# PainRegister_PWM.net
KiCad netlist of a schematic drawn in Altium Designer
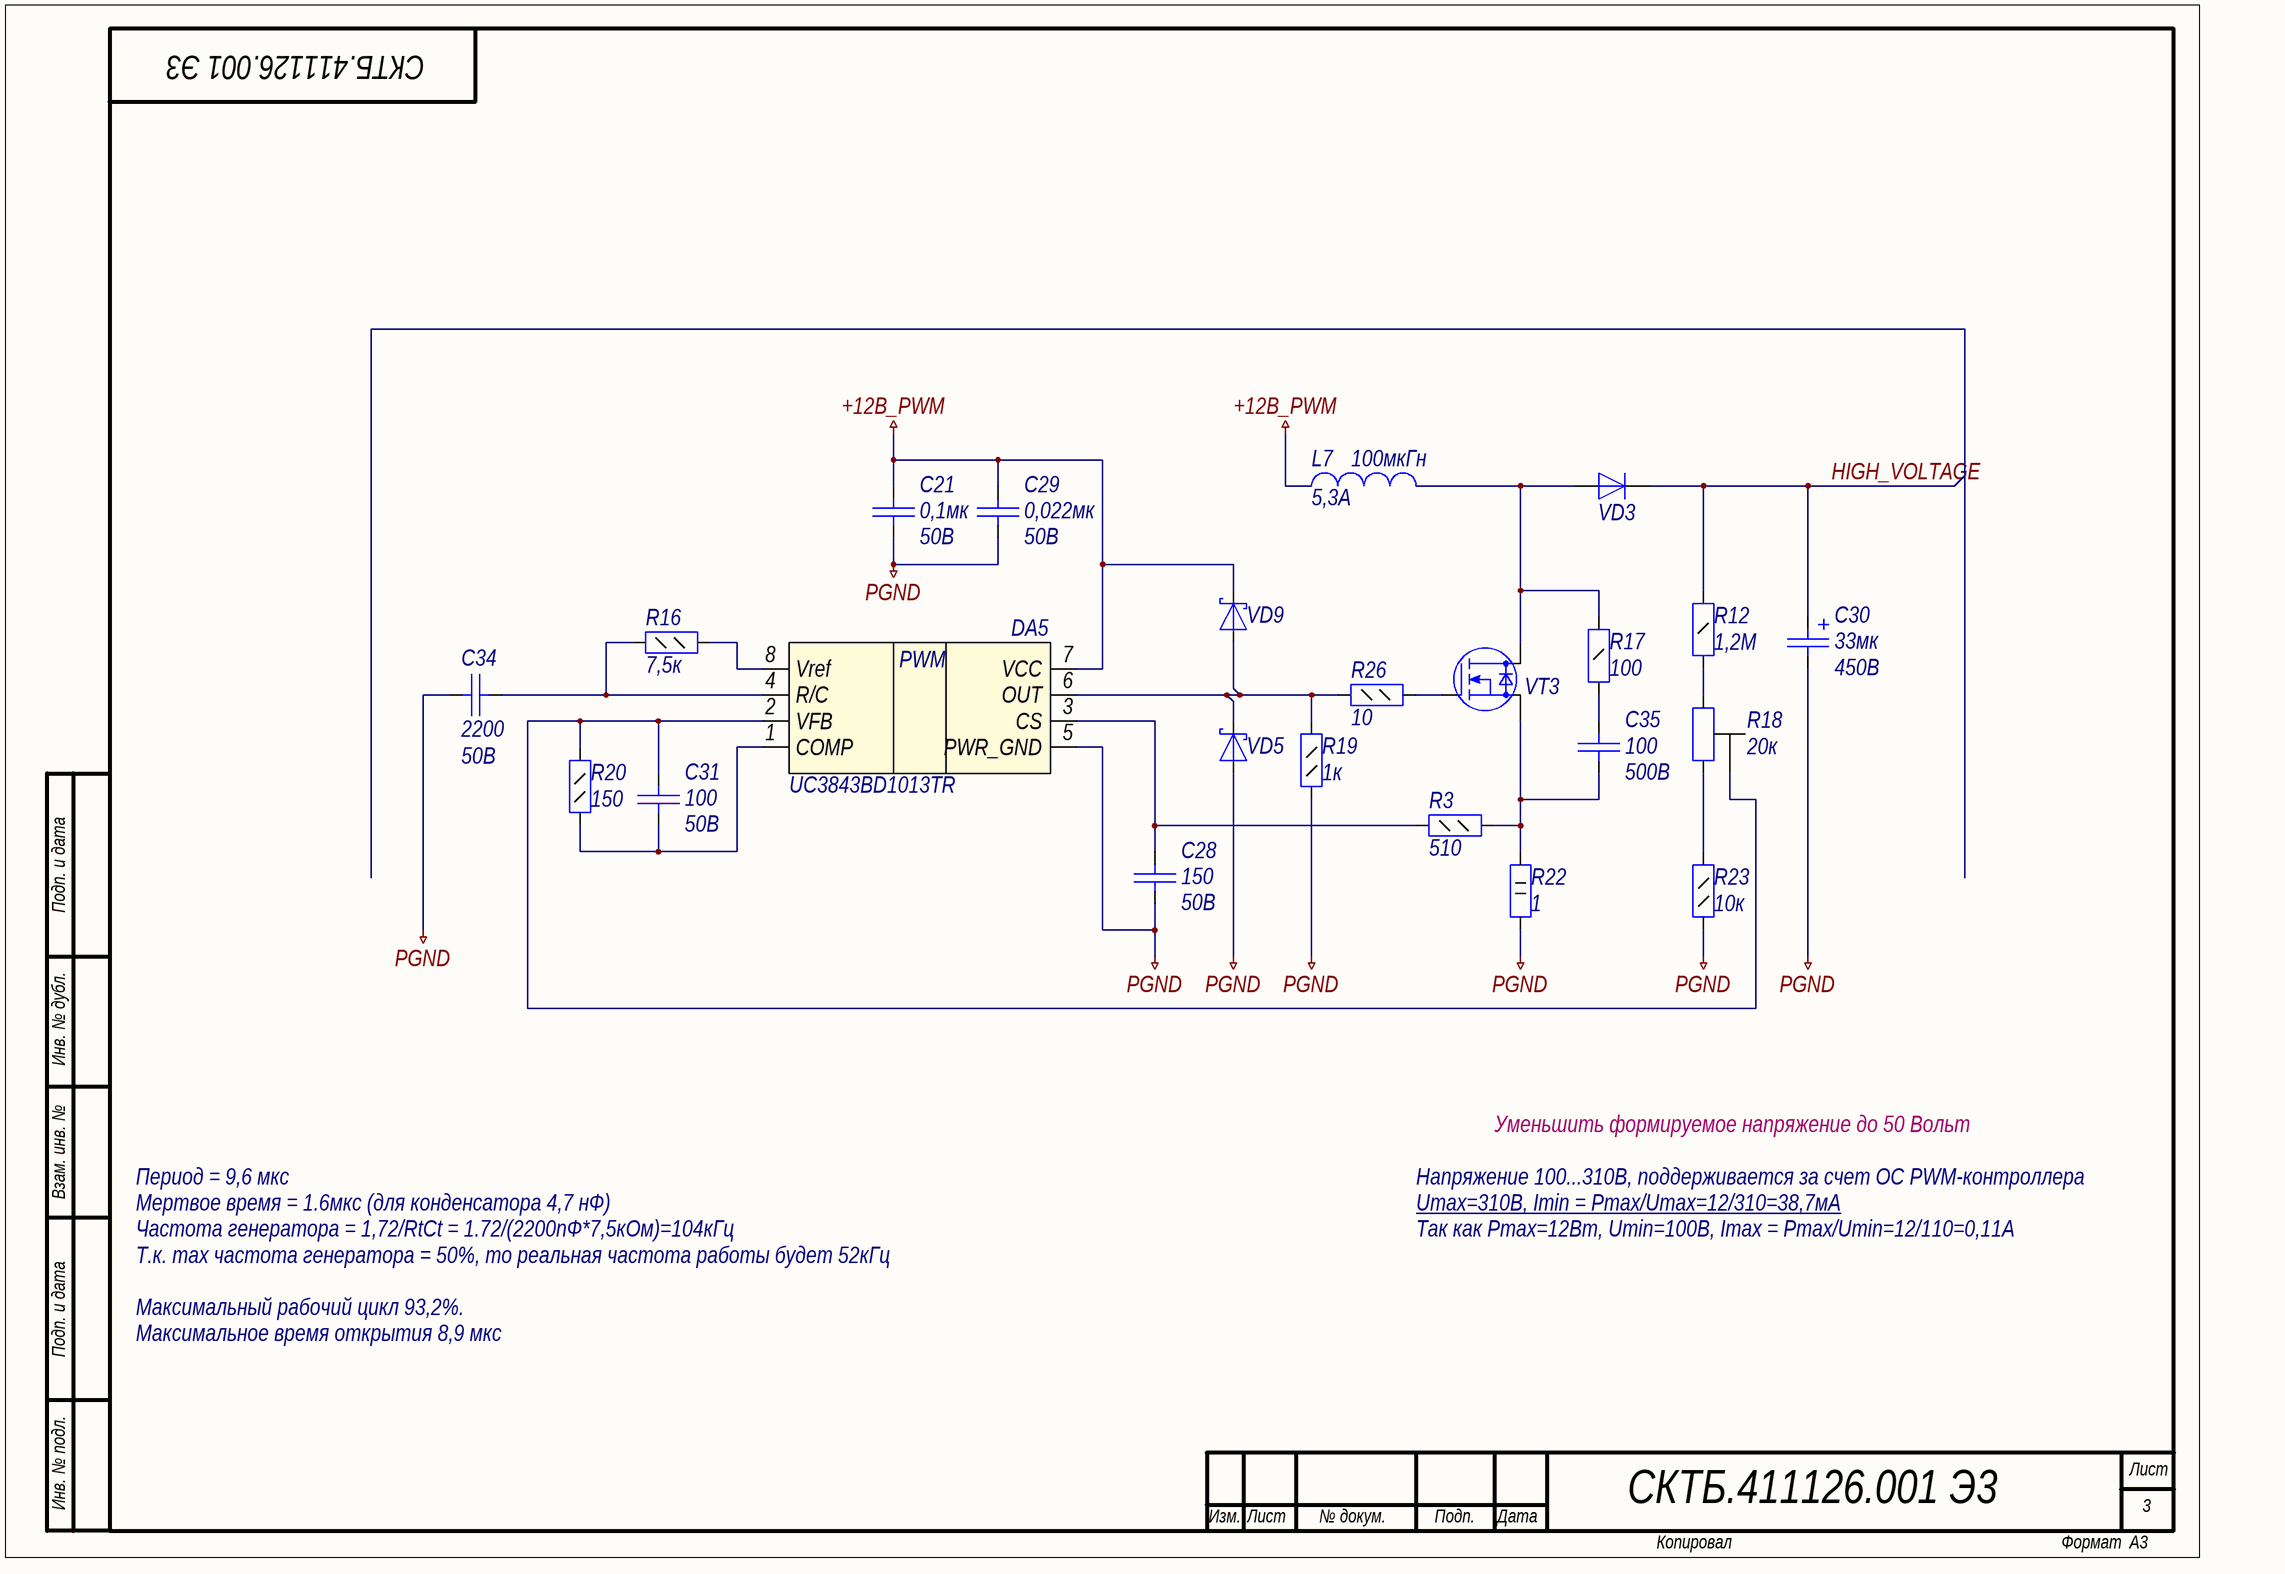
[diagram p0: PainRegister_PWM.SchDoc]

(export (version "E")
  (design (tool "Eeschema 10.0.6"))
  (components
    (comp (ref "C21")
      (value "0,1мк")
      (footprint "C0805")
      (description "Конденсатор")
      (fields
        (field (name "VOLTAGE") "50В")
        (field (name "PART NUMBER") "GRM21BR71H104KA01L ")
        (field (name "Comment") "Capacitor")
      )
      (libsource (lib "MOP44") (part "Capacitor"))
    )
    (comp (ref "C28")
      (value "150")
      (footprint "C0603")
      (description "Конденсатор")
      (fields
        (field (name "VOLTAGE") "50B")
        (field (name "PART NUMBER") "GRM1885C1H151J")
        (field (name "Comment") "Capacitor")
      )
      (libsource (lib "MOP44") (part "Capacitor"))
    )
    (comp (ref "C29")
      (value "0,022мк")
      (footprint "C1206")
      (description "Конденсатор")
      (fields
        (field (name "VOLTAGE") "50В")
        (field (name "PART NUMBER") "GRM319R71H223K")
        (field (name "Comment") "Capacitor")
      )
      (libsource (lib "MOP44") (part "Capacitor"))
    )
    (comp (ref "C30")
      (value "33мк")
      (footprint "K50-35(16X32)")
      (description "Конденсатор полярный")
      (fields
        (field (name "VOLTAGE") "450В")
        (field (name "PART NUMBER") "ECAP33uF/450V")
        (field (name "Comment") "Capacitor_pol")
      )
      (libsource (lib "MOP44") (part "Capacitor_pol"))
    )
    (comp (ref "C31")
      (value "100")
      (footprint "C0603")
      (description "Конденсатор")
      (fields
        (field (name "VOLTAGE") "50B")
        (field (name "PART NUMBER") "GRM1885C1H101J")
        (field (name "Comment") "Capacitor")
      )
      (libsource (lib "MOP44") (part "Capacitor"))
    )
    (comp (ref "C34")
      (value "2200")
      (footprint "C0805")
      (description "Конденсатор")
      (fields
        (field (name "VOLTAGE") "50В")
        (field (name "PART NUMBER") "GRM216R71H222K")
        (field (name "Comment") "Capacitor")
      )
      (libsource (lib "MOP44") (part "Capacitor"))
    )
    (comp (ref "C35")
      (value "100")
      (footprint "C1206")
      (description "Конденсатор")
      (fields
        (field (name "VOLTAGE") "500В")
        (field (name "PART NUMBER") "CC1206JRNPOBBN101")
        (field (name "Comment") "Capacitor")
      )
      (libsource (lib "MOP44") (part "Capacitor"))
    )
    (comp (ref "DA5")
      (value "UC384X")
      (footprint "SO8")
      (description "Current Mode PWM  Controller for Forward and  Flyback Applications")
      (fields (field (name "PART NUMBER") "UC3843BD1013TR"))
      (libsource (lib "MOP44") (part "UC384X"))
    )
    (comp (ref "L7")
      (value "100мкГн")
      (footprint "SRP1770TA")
      (description "EMI Suppression Filter")
      (fields
        (field (name "RATED CURRENT") "5,3A")
        (field (name "PART NUMBER") "SRP1770TA-101M")
        (field (name "Comment") "Inductor")
      )
      (libsource (lib "MOP44") (part "Inductor"))
    )
    (comp (ref "R3")
      (value "510")
      (footprint "R1206")
      (description "Резистор")
      (fields (field (name "PART NUMBER") "RC0805FR-07510RL") (field (name "POWER") "0,125Вт"))
      (libsource (lib "") (part "Resistor_0,125Вт_1"))
    )
    (comp (ref "R12")
      (value "1,2М")
      (footprint "R1206")
      (description "Резистор")
      (fields (field (name "PART NUMBER") "RC1206FR-071M2") (field (name "POWER") "0,25Вт"))
      (libsource (lib "MOP44") (part "Resistor_0,25Вт"))
    )
    (comp (ref "R16")
      (value "7,5к")
      (footprint "R0805")
      (description "Резистор")
      (fields (field (name "PART NUMBER") "RC0805FR-077K5") (field (name "POWER") "0,125Вт"))
      (libsource (lib "") (part "Resistor_0,125Вт_1"))
    )
    (comp (ref "R17")
      (value "100")
      (footprint "R1206")
      (description "Резистор")
      (fields (field (name "PART NUMBER") "RC1206FR-07100RL") (field (name "POWER") "0,25Вт"))
      (libsource (lib "MOP44") (part "Resistor_0,25Вт"))
    )
    (comp (ref "R18")
      (value "20к")
      (footprint "3296Y")
      (description "Potentiometer")
      (fields (field (name "PART NUMBER") "3296Y-1-203LF") (field (name "POWER") "0,5Вт"))
      (libsource (lib "MOP44") (part "Potentiometer"))
    )
    (comp (ref "R19")
      (value "1к")
      (footprint "R0805")
      (description "Резистор")
      (fields (field (name "PART NUMBER") "RC0805FR-071KL") (field (name "POWER") "0,125Вт"))
      (libsource (lib "MOP44") (part "Resistor_0,125Вт"))
    )
    (comp (ref "R20")
      (value "150")
      (footprint "R0805")
      (description "Резистор")
      (fields (field (name "PART NUMBER") "RC0805FR-07150RL") (field (name "POWER") "0,125Вт"))
      (libsource (lib "MOP44") (part "Resistor_0,125Вт"))
    )
    (comp (ref "R22")
      (value "1")
      (footprint "KNP-2")
      (description "Резистор")
      (fields (field (name "PART NUMBER") "KNP-2W-1KJ") (field (name "POWER") "2Вт"))
      (libsource (lib "MOP44") (part "Resistor_2Вт"))
    )
    (comp (ref "R23")
      (value "10к")
      (footprint "R0805")
      (description "Резистор")
      (fields (field (name "PART NUMBER") "RC0805FR-0710KL") (field (name "POWER") "0,125Вт"))
      (libsource (lib "MOP44") (part "Resistor_0,125Вт"))
    )
    (comp (ref "R26")
      (value "10")
      (footprint "R0805")
      (description "Резистор")
      (fields (field (name "PART NUMBER") "RC0805FR-0710RL") (field (name "POWER") "0,125Вт"))
      (libsource (lib "") (part "Resistor_0,125Вт_1"))
    )
    (comp (ref "VD3")
      (value "Diode")
      (footprint "SMA")
      (description "Диод")
      (fields (field (name "PART NUMBER") "GS1M"))
      (libsource (lib "MOP44") (part "Diode"))
    )
    (comp (ref "VD5")
      (value "DiodeSchottky")
      (footprint "SOD-123")
      (description "Диод Шоттки")
      (fields (field (name "PART NUMBER") "MBR0520LT1"))
      (libsource (lib "MOP44") (part "DiodeSchottky"))
    )
    (comp (ref "VD9")
      (value "DiodeSchottky")
      (footprint "SOD-123")
      (description "Диод Шоттки")
      (fields (field (name "PART NUMBER") "MBR0520LT1"))
      (libsource (lib "MOP44") (part "DiodeSchottky"))
    )
    (comp (ref "VT3")
      (value "N-MOSFET")
      (footprint "D2PAK")
      (fields (field (name "PART NUMBER") "IRF840ASPBF") (field (name "MANUFACTURER") "Vishay"))
      (libsource (lib "MOP44") (part "N-MOSFET"))
    )
  )
  (nets
    (net (code "1") (name "+12В_PWM") (class "Default")
      (node (ref "C21") (pin "2") (pinfunction "2_2") (pintype "passive"))
      (node (ref "C29") (pin "2") (pinfunction "2_2") (pintype "passive"))
      (node (ref "DA5") (pin "7") (pinfunction "VCC_7") (pintype "passive"))
      (node (ref "L7") (pin "1") (pinfunction "1_1") (pintype "passive"))
      (node (ref "VD9") (pin "1") (pinfunction "K_1") (pintype "passive"))
    )
    (net (code "2") (name "/HIGH_VOLTAGE") (class "Default")
      (node (ref "C30") (pin "1") (pinfunction "1_1") (pintype "passive"))
      (node (ref "R12") (pin "2") (pinfunction "2_2") (pintype "passive"))
      (node (ref "VD3") (pin "1") (pinfunction "K_1") (pintype "passive"))
    )
    (net (code "3") (name "Net-(C35-Pad2)") (class "Default")
      (node (ref "C35") (pin "2") (pinfunction "2_2") (pintype "passive"))
      (node (ref "R17") (pin "1") (pinfunction "1_1") (pintype "passive"))
    )
    (net (code "4") (name "Net-(DA5-COMP)") (class "Default")
      (node (ref "C31") (pin "1") (pinfunction "1_1") (pintype "passive"))
      (node (ref "DA5") (pin "1") (pinfunction "COMP_1") (pintype "passive"))
      (node (ref "R20") (pin "1") (pinfunction "1_1") (pintype "passive"))
    )
    (net (code "5") (name "Net-(DA5-CS)") (class "Default")
      (node (ref "C28") (pin "2") (pinfunction "2_2") (pintype "passive"))
      (node (ref "DA5") (pin "3") (pinfunction "CS_3") (pintype "passive"))
      (node (ref "R3") (pin "1") (pinfunction "1_1") (pintype "passive"))
    )
    (net (code "6") (name "Net-(DA5-OUT)") (class "Default")
      (node (ref "DA5") (pin "6") (pinfunction "OUT_6") (pintype "passive"))
      (node (ref "R19") (pin "2") (pinfunction "2_2") (pintype "passive"))
      (node (ref "R26") (pin "1") (pinfunction "1_1") (pintype "passive"))
      (node (ref "VD5") (pin "1") (pinfunction "K_1") (pintype "passive"))
      (node (ref "VD9") (pin "2") (pinfunction "A_2") (pintype "passive"))
    )
    (net (code "7") (name "Net-(DA5-R{slash}C)") (class "Default")
      (node (ref "C34") (pin "2") (pinfunction "2_2") (pintype "passive"))
      (node (ref "DA5") (pin "4") (pinfunction "R/C_4") (pintype "passive"))
      (node (ref "R16") (pin "1") (pinfunction "1_1") (pintype "passive"))
    )
    (net (code "8") (name "Net-(DA5-VFB)") (class "Default")
      (node (ref "C31") (pin "2") (pinfunction "2_2") (pintype "passive"))
      (node (ref "DA5") (pin "2") (pinfunction "VFB_2") (pintype "passive"))
      (node (ref "R18") (pin "2") (pinfunction "2_2") (pintype "passive"))
      (node (ref "R20") (pin "2") (pinfunction "2_2") (pintype "passive"))
    )
    (net (code "9") (name "Net-(DA5-Vref)") (class "Default")
      (node (ref "DA5") (pin "8") (pinfunction "Vref_8") (pintype "passive"))
      (node (ref "R16") (pin "2") (pinfunction "2_2") (pintype "passive"))
    )
    (net (code "10") (name "Net-(R12-Pad1)") (class "Default")
      (node (ref "R12") (pin "1") (pinfunction "1_1") (pintype "passive"))
      (node (ref "R18") (pin "1") (pinfunction "1_1") (pintype "passive"))
    )
    (net (code "11") (name "Net-(R18-Pad3)") (class "Default")
      (node (ref "R18") (pin "3") (pinfunction "3_3") (pintype "passive"))
      (node (ref "R23") (pin "2") (pinfunction "2_2") (pintype "passive"))
    )
    (net (code "12") (name "Net-(R22-5)") (class "Default")
      (node (ref "C35") (pin "1") (pinfunction "1_1") (pintype "passive"))
      (node (ref "R22") (pin "2") (pinfunction "5_2") (pintype "passive"))
      (node (ref "R3") (pin "2") (pinfunction "2_2") (pintype "passive"))
      (node (ref "VT3") (pin "3") (pinfunction "S_3") (pintype "passive"))
    )
    (net (code "13") (name "Net-(VD3-A)") (class "Default")
      (node (ref "L7") (pin "2") (pinfunction "2_2") (pintype "passive"))
      (node (ref "R17") (pin "2") (pinfunction "2_2") (pintype "passive"))
      (node (ref "VD3") (pin "2") (pinfunction "A_2") (pintype "passive"))
      (node (ref "VT3") (pin "2") (pinfunction "D_2") (pintype "passive"))
    )
    (net (code "14") (name "Net-(VT3-G)") (class "Default")
      (node (ref "R26") (pin "2") (pinfunction "2_2") (pintype "passive"))
      (node (ref "VT3") (pin "1") (pinfunction "G_1") (pintype "passive"))
    )
    (net (code "15") (name "PGND") (class "Default")
      (node (ref "C21") (pin "1") (pinfunction "1_1") (pintype "passive"))
      (node (ref "C28") (pin "1") (pinfunction "1_1") (pintype "passive"))
      (node (ref "C29") (pin "1") (pinfunction "1_1") (pintype "passive"))
      (node (ref "C30") (pin "2") (pinfunction "2_2") (pintype "passive"))
      (node (ref "C34") (pin "1") (pinfunction "1_1") (pintype "passive"))
      (node (ref "DA5") (pin "5") (pinfunction "PWR_GND_5") (pintype "passive"))
      (node (ref "R19") (pin "1") (pinfunction "1_1") (pintype "passive"))
      (node (ref "R22") (pin "1") (pinfunction "1_1") (pintype "passive"))
      (node (ref "R23") (pin "1") (pinfunction "1_1") (pintype "passive"))
      (node (ref "VD5") (pin "2") (pinfunction "A_2") (pintype "passive"))
    )
  )
)
